# Motor_Control_-_Phase_C.net
KiCad netlist of a schematic drawn in Altium Designer
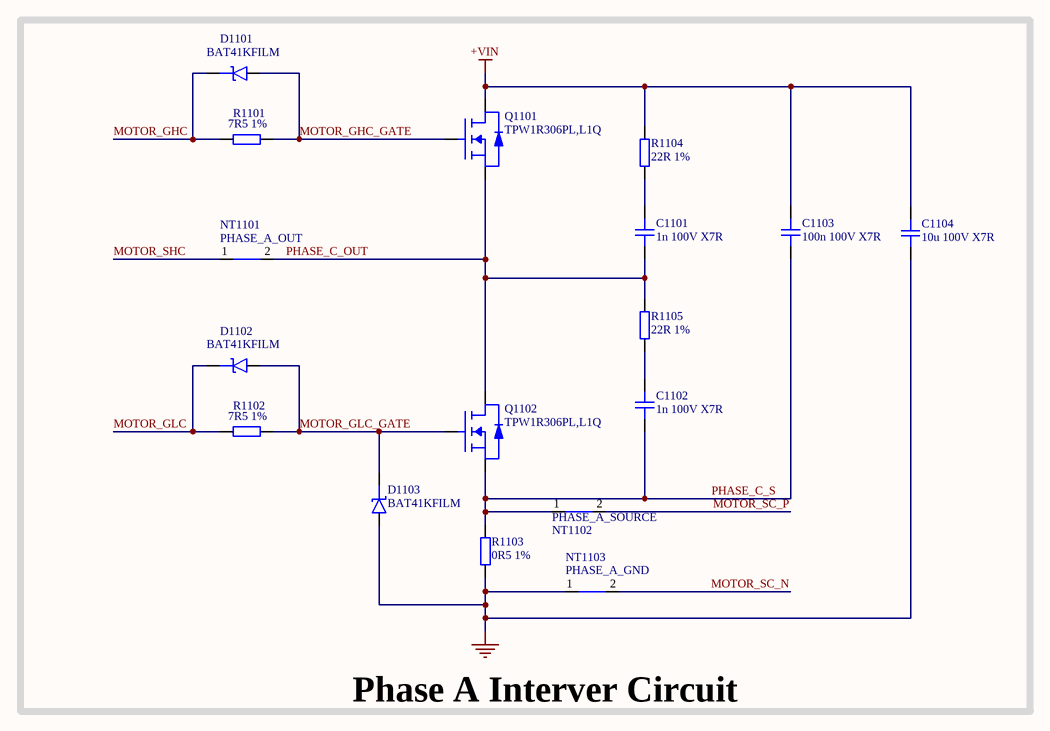
[diagram p0: Motor Control - Phase C.SchDoc]

(export (version "E")
  (design (tool "Eeschema 10.0.6"))
  (components
    (comp (ref "C1101")
      (value "1n 100V X7R")
      (footprint "CAP_0805")
      (description "Capacitor SMD 0805")
      (fields
        (field (name "MANUFACTURER") "Kyocera AVX")
        (field (name "MANUFACTURER PART NUMBER") "08051C102JAT2A")
      )
      (libsource (lib "Schematic-Lib-PhilsLab") (part "CAP_0805"))
    )
    (comp (ref "C1102")
      (value "1n 100V X7R")
      (footprint "CAP_0805")
      (description "Capacitor SMD 0805")
      (fields
        (field (name "MANUFACTURER") "Kyocera AVX")
        (field (name "MANUFACTURER PART NUMBER") "08051C102JAT2A")
      )
      (libsource (lib "Schematic-Lib-PhilsLab") (part "CAP_0805"))
    )
    (comp (ref "C1103")
      (value "100n 100V X7R")
      (footprint "CAP_1206")
      (description "Capacitor SMD 1206")
      (fields
        (field (name "MANUFACTURER") "YAGEO")
        (field (name "MANUFACTURER PART NUMBER") "CC1206JKX7R0BB104")
      )
      (libsource (lib "Schematic-Lib-PhilsLab") (part "CAP_1206"))
    )
    (comp (ref "C1104")
      (value "10u 100V X7R")
      (footprint "CAP_1210")
      (description "Capacitor SMD 1210")
      (fields
        (field (name "MANUFACTURER") "PSA(Prosperity Dielectrics)")
        (field (name "MANUFACTURER PART NUMBER") "FS32X106K101EGG")
      )
      (libsource (lib "Schematic-Lib-PhilsLab") (part "CAP_1210"))
    )
    (comp (ref "D1101")
      (value "BAT41KFILM")
      (footprint "SOD-523")
      (description "Diode Schottky SMD SOD-323")
      (fields (field (name "MANUFACTURER") "STMicroelectronics"))
      (libsource (lib "Schematic-Lib-PhilsLab") (part "D_SCHOTTKY_SOD_523"))
    )
    (comp (ref "D1102")
      (value "BAT41KFILM")
      (footprint "SOD-523")
      (description "Diode Schottky SMD SOD-323")
      (fields (field (name "MANUFACTURER") "STMicroelectronics"))
      (libsource (lib "Schematic-Lib-PhilsLab") (part "D_SCHOTTKY_SOD_523"))
    )
    (comp (ref "D1103")
      (value "BAT41KFILM")
      (footprint "SOD-523")
      (description "Diode Schottky SMD SOD-323")
      (fields (field (name "MANUFACTURER") "STMicroelectronics"))
      (libsource (lib "Schematic-Lib-PhilsLab") (part "D_SCHOTTKY_SOD_523"))
    )
    (comp (ref "NT1101")
      (value "PHASE_A_OUT")
      (footprint "NETTIE_SMD")
      (description "Net Tie SMD")
      (libsource (lib "Schematic-Lib-PhilsLab") (part "NetTie_SMD"))
    )
    (comp (ref "NT1102")
      (value "PHASE_A_SOURCE")
      (footprint "NETTIE_SMD")
      (description "Net Tie SMD")
      (libsource (lib "Schematic-Lib-PhilsLab") (part "NetTie_SMD"))
    )
    (comp (ref "NT1103")
      (value "PHASE_A_GND")
      (footprint "NETTIE_SMD")
      (description "Net Tie SMD")
      (libsource (lib "Schematic-Lib-PhilsLab") (part "NetTie_SMD"))
    )
    (comp (ref "Q1101")
      (value "TPW1R306PL,L1Q")
      (footprint "PowerPAK-SO-8")
      (description "MOSFET N-Channel Vds=30V Id=351A Rds=470uR")
      (fields
        (field (name "MANUFACTURER") "Vishay")
        (field (name "MANUFACTURER PART NUMBER") "SIR500DP-T1-RE3")
      )
      (libsource (lib "Schematic-Lib-PhilsLab") (part "SIR500DP-T1-RE3"))
    )
    (comp (ref "Q1102")
      (value "TPW1R306PL,L1Q")
      (footprint "PowerPAK-SO-8")
      (description "MOSFET N-Channel Vds=30V Id=351A Rds=470uR")
      (fields
        (field (name "MANUFACTURER") "Vishay")
        (field (name "MANUFACTURER PART NUMBER") "SIR500DP-T1-RE3")
      )
      (libsource (lib "Schematic-Lib-PhilsLab") (part "SIR500DP-T1-RE3"))
    )
    (comp (ref "R1101")
      (value "7R5 1%")
      (footprint "RES_0603")
      (description "Resistor SMD 0603")
      (fields
        (field (name "MANUFACTURER") "PANASONIC")
        (field (name "MANUFACTURER PART NUMBER") "ERJPA3J7R5V")
      )
      (libsource (lib "Schematic-Lib-PhilsLab") (part "RES_0603"))
    )
    (comp (ref "R1102")
      (value "7R5 1%")
      (footprint "RES_0603")
      (description "Resistor SMD 0603")
      (fields
        (field (name "MANUFACTURER") "PANASONIC")
        (field (name "MANUFACTURER PART NUMBER") "ERJPA3J7R5V")
      )
      (libsource (lib "Schematic-Lib-PhilsLab") (part "RES_0603"))
    )
    (comp (ref "R1103")
      (value "0R5 1%")
      (footprint "RES_1206")
      (description "Resistor SMD 1206")
      (fields
        (field (name "MANUFACTURER") "Milliohm")
        (field (name "MANUFACTURER PART NUMBER") "HoSRX1206-3W-0.5mR-1%")
      )
      (libsource (lib "Schematic-Lib-PhilsLab") (part "RES_1206"))
    )
    (comp (ref "R1104")
      (value "22R 1%")
      (footprint "RES_0805")
      (description "Resistor SMD 0805")
      (fields
        (field (name "MANUFACTURER") "Viking Tech")
        (field (name "MANUFACTURER PART NUMBER") "ARG05FTC0220")
      )
      (libsource (lib "Schematic-Lib-PhilsLab") (part "RES_0805"))
    )
    (comp (ref "R1105")
      (value "22R 1%")
      (footprint "RES_0805")
      (description "Resistor SMD 0805")
      (fields
        (field (name "MANUFACTURER") "Viking Tech")
        (field (name "MANUFACTURER PART NUMBER") "ARG05FTC0220")
      )
      (libsource (lib "Schematic-Lib-PhilsLab") (part "RES_0805"))
    )
  )
  (nets
    (net (code "1") (name "+VIN") (class "Default")
      (node (ref "C1103") (pin "2") (pinfunction "2_2") (pintype "passive"))
      (node (ref "C1104") (pin "2") (pinfunction "2_2") (pintype "passive"))
      (node (ref "Q1101") (pin "D") (pinfunction "D_D") (pintype "passive"))
      (node (ref "R1104") (pin "2") (pinfunction "2_2") (pintype "passive"))
    )
    (net (code "2") (name "/MOTOR_GHC") (class "Default")
      (node (ref "D1101") (pin "K") (pinfunction "K_K") (pintype "passive"))
      (node (ref "R1101") (pin "1") (pinfunction "1_1") (pintype "passive"))
    )
    (net (code "3") (name "/MOTOR_GHC_GATE") (class "Default")
      (node (ref "D1101") (pin "A") (pinfunction "A_A") (pintype "passive"))
      (node (ref "Q1101") (pin "G") (pinfunction "G_G") (pintype "passive"))
      (node (ref "R1101") (pin "2") (pinfunction "2_2") (pintype "passive"))
    )
    (net (code "4") (name "/MOTOR_GLC") (class "Default")
      (node (ref "D1102") (pin "K") (pinfunction "K_K") (pintype "passive"))
      (node (ref "R1102") (pin "1") (pinfunction "1_1") (pintype "passive"))
    )
    (net (code "5") (name "/MOTOR_GLC_GATE") (class "Default")
      (node (ref "D1102") (pin "A") (pinfunction "A_A") (pintype "passive"))
      (node (ref "D1103") (pin "K") (pinfunction "K_K") (pintype "passive"))
      (node (ref "Q1102") (pin "G") (pinfunction "G_G") (pintype "passive"))
      (node (ref "R1102") (pin "2") (pinfunction "2_2") (pintype "passive"))
    )
    (net (code "6") (name "/MOTOR_SC_N") (class "Default")
      (node (ref "NT1103") (pin "2") (pinfunction "2_2") (pintype "passive"))
    )
    (net (code "7") (name "/MOTOR_SC_P") (class "Default")
      (node (ref "NT1102") (pin "2") (pinfunction "2_2") (pintype "passive"))
    )
    (net (code "8") (name "/MOTOR_SHC") (class "Default")
      (node (ref "NT1101") (pin "1") (pinfunction "1_1") (pintype "passive"))
    )
    (net (code "9") (name "/PHASE_C_OUT") (class "Default")
      (node (ref "C1101") (pin "1") (pinfunction "1_1") (pintype "passive"))
      (node (ref "NT1101") (pin "2") (pinfunction "2_2") (pintype "passive"))
      (node (ref "Q1101") (pin "S") (pinfunction "S_S") (pintype "passive"))
      (node (ref "Q1102") (pin "D") (pinfunction "D_D") (pintype "passive"))
      (node (ref "R1105") (pin "2") (pinfunction "2_2") (pintype "passive"))
    )
    (net (code "10") (name "/PHASE_C_S") (class "Default")
      (node (ref "C1102") (pin "1") (pinfunction "1_1") (pintype "passive"))
      (node (ref "C1103") (pin "1") (pinfunction "1_1") (pintype "passive"))
      (node (ref "NT1102") (pin "1") (pinfunction "1_1") (pintype "passive"))
      (node (ref "Q1102") (pin "S") (pinfunction "S_S") (pintype "passive"))
      (node (ref "R1103") (pin "2") (pinfunction "2_2") (pintype "passive"))
    )
    (net (code "11") (name "GND") (class "Default")
      (node (ref "C1104") (pin "1") (pinfunction "1_1") (pintype "passive"))
      (node (ref "D1103") (pin "A") (pinfunction "A_A") (pintype "passive"))
      (node (ref "NT1103") (pin "1") (pinfunction "1_1") (pintype "passive"))
      (node (ref "R1103") (pin "1") (pinfunction "1_1") (pintype "passive"))
    )
    (net (code "12") (name "Net-(C1101-Pad2)") (class "Default")
      (node (ref "C1101") (pin "2") (pinfunction "2_2") (pintype "passive"))
      (node (ref "R1104") (pin "1") (pinfunction "1_1") (pintype "passive"))
    )
    (net (code "13") (name "Net-(C1102-Pad2)") (class "Default")
      (node (ref "C1102") (pin "2") (pinfunction "2_2") (pintype "passive"))
      (node (ref "R1105") (pin "1") (pinfunction "1_1") (pintype "passive"))
    )
  )
)
